# Main.net
KiCad netlist of a schematic drawn in Altium Designer
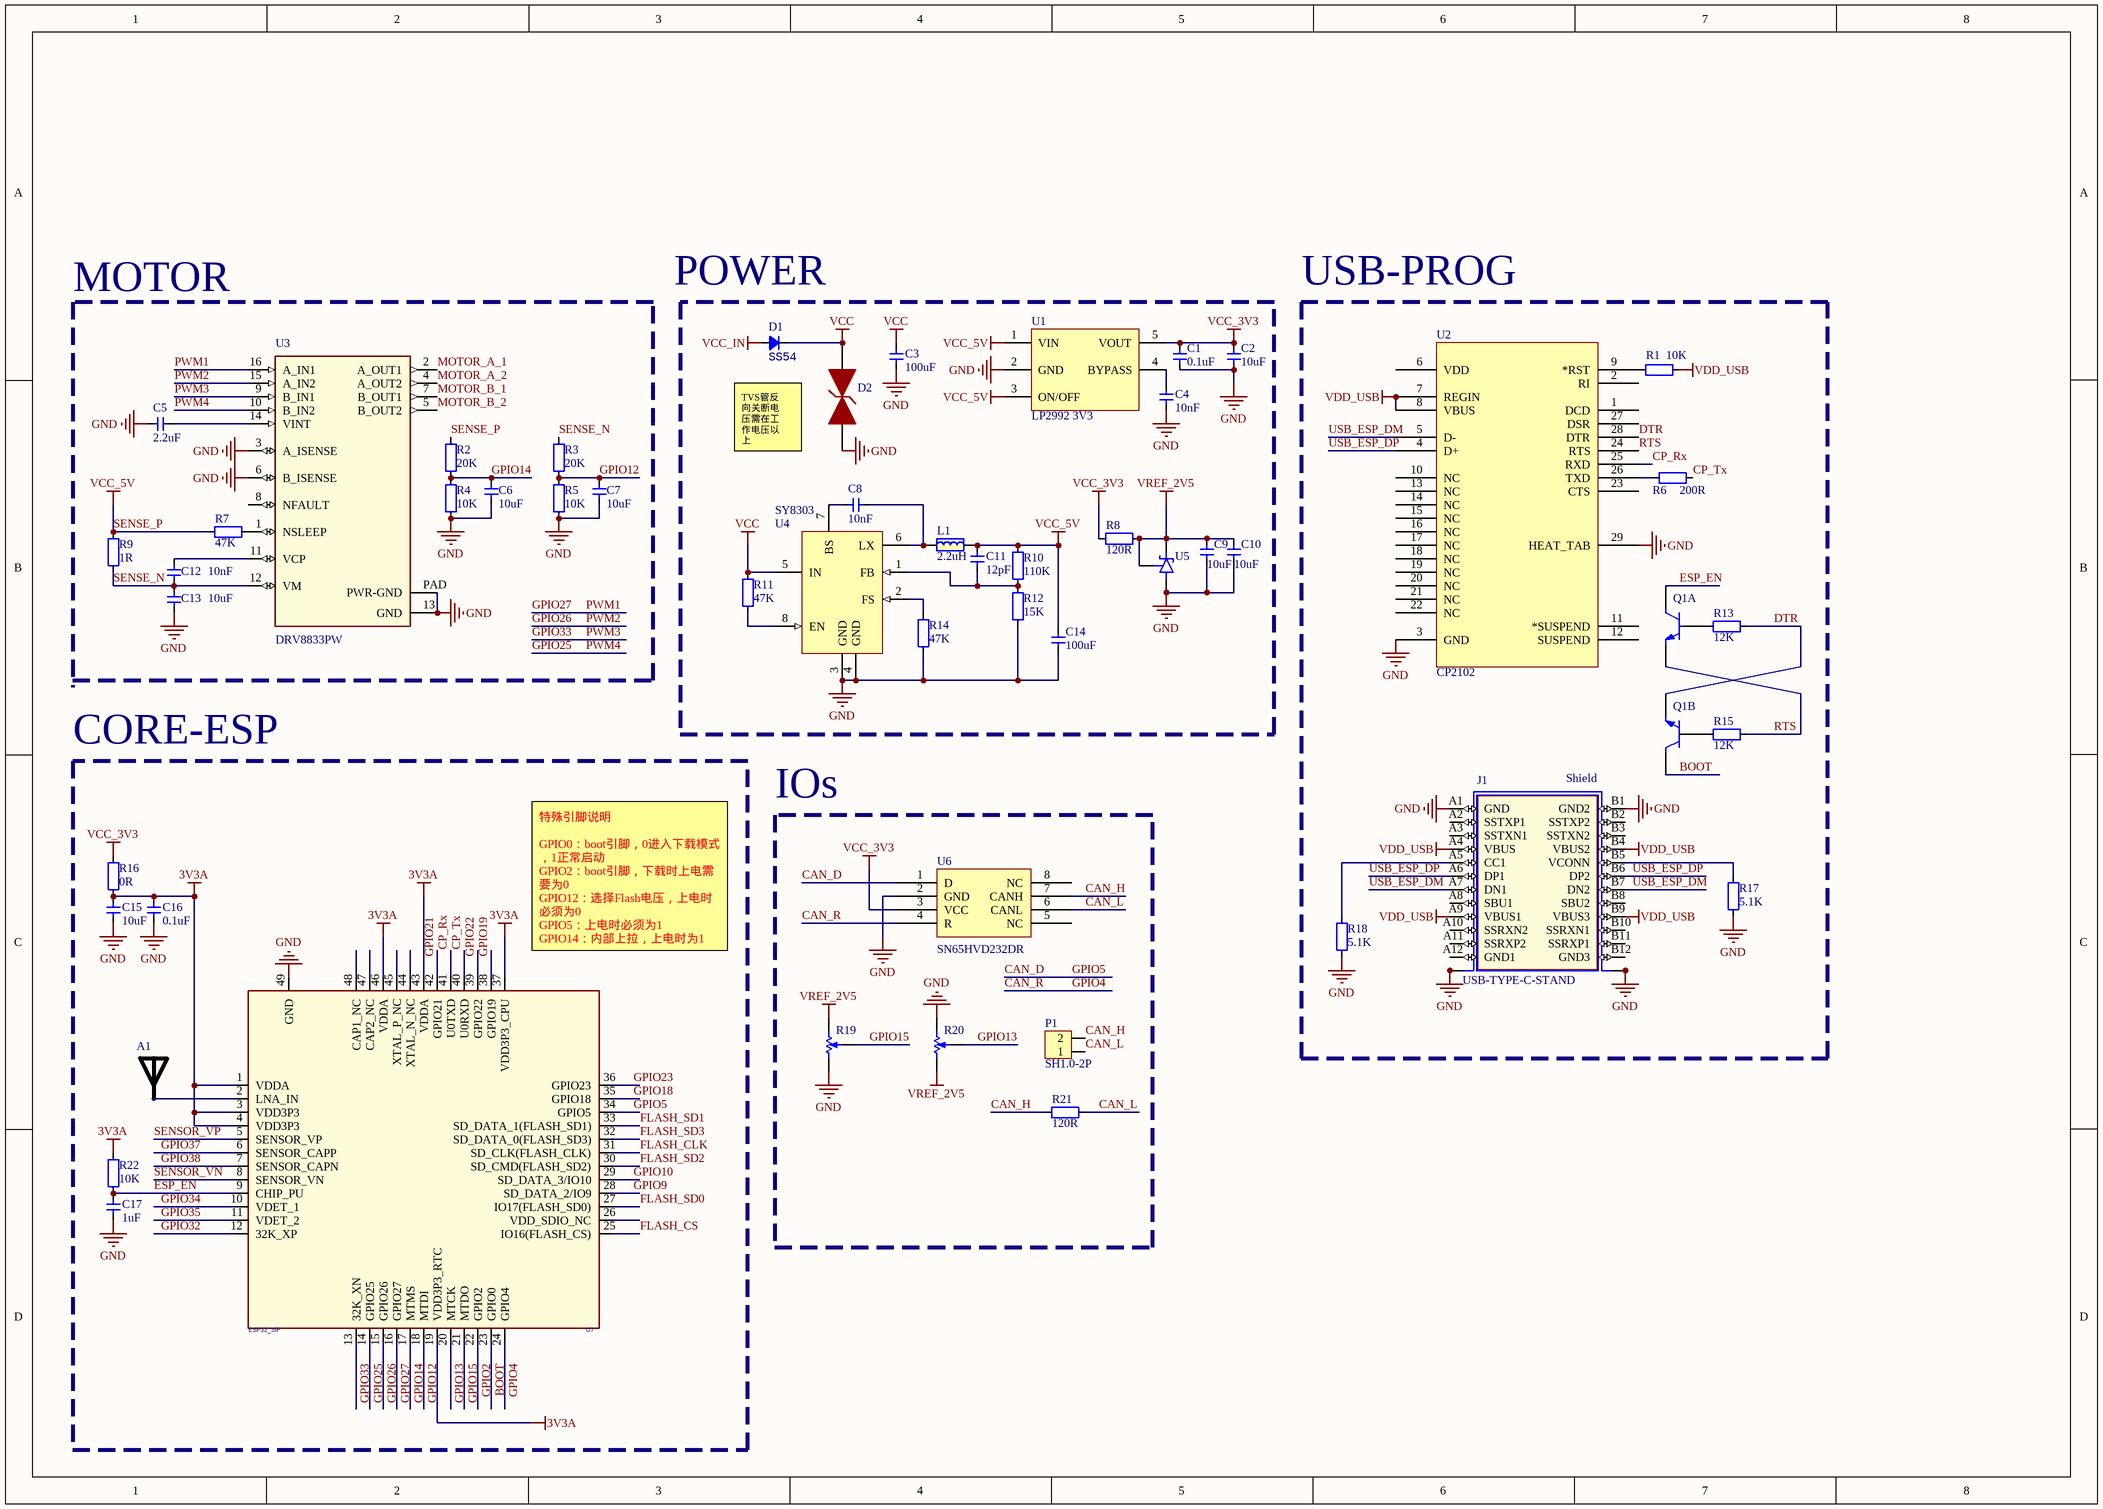
[diagram p0: Main.SchDoc]

(export (version "E")
  (design (tool "Eeschema 10.0.6"))
  (components
    (comp (ref "A1")
      (value "RAINSUN")
      (footprint "ANT-Rainsun-AN5120")
      (libsource (lib "MyPcbLib") (part "ANT-Rainsun-AP5120"))
    )
    (comp (ref "C1")
      (value "0.1uF")
      (footprint "CAP_0402")
      (description "Capacitor")
      (libsource (lib "MyPcbLib") (part "电容-0402"))
    )
    (comp (ref "C2")
      (value "10uF")
      (footprint "CAP_0402")
      (description "Capacitor")
      (libsource (lib "MyPcbLib") (part "电容-0402"))
    )
    (comp (ref "C3")
      (value "100uF")
      (footprint "1206-CAP")
      (description "Capacitor")
      (libsource (lib "MyPcbLib") (part "电容-1206"))
    )
    (comp (ref "C4")
      (value "10nF")
      (footprint "CAP_0402")
      (description "Capacitor")
      (libsource (lib "MyPcbLib") (part "电容-0402"))
    )
    (comp (ref "C5")
      (value "2.2uF")
      (footprint "CAP_0402")
      (description "Capacitor")
      (libsource (lib "MyPcbLib") (part "电容-0402"))
    )
    (comp (ref "C6")
      (value "10uF")
      (footprint "CAP_0402")
      (description "Capacitor")
      (libsource (lib "MyPcbLib") (part "电容-0402"))
    )
    (comp (ref "C7")
      (value "10uF")
      (footprint "CAP_0402")
      (description "Capacitor")
      (libsource (lib "MyPcbLib") (part "电容-0402"))
    )
    (comp (ref "C8")
      (value "10nF")
      (footprint "CAP_0402")
      (description "Capacitor")
      (libsource (lib "MyPcbLib") (part "电容-0402"))
    )
    (comp (ref "C9")
      (value "10uF")
      (footprint "CAP_0402")
      (description "Capacitor")
      (libsource (lib "MyPcbLib") (part "电容-0402"))
    )
    (comp (ref "C10")
      (value "10uF")
      (footprint "CAP_0402")
      (description "Capacitor")
      (libsource (lib "MyPcbLib") (part "电容-0402"))
    )
    (comp (ref "C11")
      (value "12pF")
      (footprint "CAP_0402")
      (description "Capacitor")
      (libsource (lib "MyPcbLib") (part "电容-0402"))
    )
    (comp (ref "C12")
      (value "10nF")
      (footprint "CAP_0402")
      (description "Capacitor")
      (libsource (lib "MyPcbLib") (part "电容-0402"))
    )
    (comp (ref "C13")
      (value "10uF")
      (footprint "CAP_0402")
      (description "Capacitor")
      (libsource (lib "MyPcbLib") (part "电容-0402"))
    )
    (comp (ref "C14")
      (value "100uF")
      (footprint "CAP_0402")
      (description "Capacitor")
      (libsource (lib "MyPcbLib") (part "电容-0402"))
    )
    (comp (ref "C15")
      (value "10uF")
      (footprint "CAP_0402")
      (description "Capacitor")
      (libsource (lib "MyPcbLib") (part "电容-0402"))
    )
    (comp (ref "C16")
      (value "0.1uF")
      (footprint "CAP_0402")
      (description "Capacitor")
      (libsource (lib "MyPcbLib") (part "电容-0402"))
    )
    (comp (ref "C17")
      (value "1uF")
      (footprint "CAP_0402")
      (description "Capacitor")
      (libsource (lib "MyPcbLib") (part "电容-0402"))
    )
    (comp (ref "D1")
      (value "SS54")
      (footprint "DO-214AC")
      (description "Diode")
      (libsource (lib "KitSprout") (part "Diode_SMA"))
    )
    (comp (ref "D2")
      (value "SMBJ28CA")
      (footprint "SMBJ-CA_MFG")
      (libsource (lib "MyPcbLib") (part "SMBJ28CA"))
    )
    (comp (ref "J1")
      (value "USB-TYPE-C-STAND")
      (footprint "USB-TYPE-C-STAND")
      (fields (field (name "MP") "632722110112") (field (name "MF") "Wurth Electronics"))
      (libsource (lib "MyPcbLib") (part "USB-TYPE-C-STAND"))
    )
    (comp (ref "L1") (value "2.2uH") (footprint "IND_CD74") (libsource (lib "MyPcbLib") (part "电感")))
    (comp (ref "P1") (value "SH1.0-2P") (footprint "SH1.0-2P") (libsource (lib "MyPcbLib") (part "SH1.0-2P")))
    (comp (ref "Q1")
      (value "BC847BVC-7")
      (footprint "SOT563-6")
      (libsource (lib "MyPcbLib") (part "BC847BVC-7"))
    )
    (comp (ref "R1")
      (value "10K")
      (footprint "RES_0402")
      (description "Resistor")
      (libsource (lib "") (part "电阻-0402_2"))
    )
    (comp (ref "R2")
      (value "20K")
      (footprint "RES_0402")
      (description "Resistor")
      (libsource (lib "") (part "电阻-0402_1"))
    )
    (comp (ref "R3")
      (value "20K")
      (footprint "RES_0402")
      (description "Resistor")
      (libsource (lib "") (part "电阻-0402_1"))
    )
    (comp (ref "R4")
      (value "10K")
      (footprint "RES_0402")
      (description "Resistor")
      (libsource (lib "") (part "电阻-0402_1"))
    )
    (comp (ref "R5")
      (value "10K")
      (footprint "RES_0402")
      (description "Resistor")
      (libsource (lib "") (part "电阻-0402_1"))
    )
    (comp (ref "R6")
      (value "200R")
      (footprint "RES_0402")
      (description "Resistor")
      (libsource (lib "") (part "电阻-0402_2"))
    )
    (comp (ref "R7")
      (value "47K")
      (footprint "RES_0402")
      (description "Resistor")
      (libsource (lib "") (part "电阻-0402_2"))
    )
    (comp (ref "R8")
      (value "120R")
      (footprint "RES_0402")
      (description "Resistor")
      (libsource (lib "") (part "电阻-0402_3"))
    )
    (comp (ref "R9")
      (value "1R")
      (footprint "1206-RES")
      (description "Resistor")
      (libsource (lib "MyPcbLib") (part "电阻-1206"))
    )
    (comp (ref "R10")
      (value "110K")
      (footprint "RES_0402")
      (description "Resistor")
      (libsource (lib "MyPcbLib") (part "电阻-0402"))
    )
    (comp (ref "R11")
      (value "47K")
      (footprint "RES_0402")
      (description "Resistor")
      (libsource (lib "MyPcbLib") (part "电阻-0402"))
    )
    (comp (ref "R12")
      (value "15K")
      (footprint "RES_0402")
      (description "Resistor")
      (libsource (lib "MyPcbLib") (part "电阻-0402"))
    )
    (comp (ref "R13")
      (value "12K")
      (footprint "RES_0402")
      (description "Resistor")
      (libsource (lib "") (part "电阻-0402_2"))
    )
    (comp (ref "R14")
      (value "47K")
      (footprint "RES_0402")
      (description "Resistor")
      (libsource (lib "MyPcbLib") (part "电阻-0402"))
    )
    (comp (ref "R15")
      (value "12K")
      (footprint "RES_0402")
      (description "Resistor")
      (libsource (lib "") (part "电阻-0402_2"))
    )
    (comp (ref "R16")
      (value "0R")
      (footprint "RES_0402")
      (description "Resistor")
      (libsource (lib "MyPcbLib") (part "电阻-0402"))
    )
    (comp (ref "R17")
      (value "5.1K")
      (footprint "RES_0402")
      (description "Resistor")
      (libsource (lib "MyPcbLib") (part "电阻-0402"))
    )
    (comp (ref "R18")
      (value "5.1K")
      (footprint "RES_0402")
      (description "Resistor")
      (libsource (lib "MyPcbLib") (part "电阻-0402"))
    )
    (comp (ref "R19")
      (value "ALPS-角度传感器")
      (footprint "ALPS-角度传感器")
      (fields (field (name "PUBLISHER") "Altium Limited"))
      (libsource (lib "MyPcbLib") (part "ALPS-角度传感器"))
    )
    (comp (ref "R20")
      (value "ALPS-角度传感器")
      (footprint "ALPS-角度传感器")
      (fields (field (name "PUBLISHER") "Altium Limited"))
      (libsource (lib "MyPcbLib") (part "ALPS-角度传感器"))
    )
    (comp (ref "R21")
      (value "120R")
      (footprint "RES_0402")
      (description "Resistor")
      (libsource (lib "") (part "电阻-0402_2"))
    )
    (comp (ref "R22")
      (value "10K")
      (footprint "RES_0402")
      (description "Resistor")
      (libsource (lib "MyPcbLib") (part "电阻-0402"))
    )
    (comp (ref "U1")
      (value "LP2992 3V3")
      (footprint "SOT23-5")
      (description "LDO")
      (libsource (lib "mLib") (part "LP2992"))
    )
    (comp (ref "U2")
      (value "CP2102")
      (footprint "QFN-28")
      (description "USB转TTL")
      (libsource (lib "mLib") (part "CP2102"))
    )
    (comp (ref "U3") (value "DRV8833PW") (footprint "TSSOP-16") (libsource (lib "mLib") (part "DRV8833PW")))
    (comp (ref "U4")
      (value "SY8303")
      (footprint "SOT23-8")
      (description "DC-DC")
      (fields
        (field (name "PARTNUMBER") "LT3469ETS8#TRMPBF")
        (field (name "MANUFACTURER") "Linear Technology")
      )
      (libsource (lib "MyPcbLib") (part "SY8303"))
    )
    (comp (ref "U5")
      (value "TL431IDBZT")
      (footprint "SOT23-3")
      (description "Adjustable precision shunt regulator 3-SOT-23 -40 to 85")
      (fields (field (name "MF") "Texas Instruments"))
      (libsource (lib "MyPcbLib") (part "TL431IDBZT"))
    )
    (comp (ref "U6")
      (value "SN65HVD232D")
      (footprint "SO-8")
      (fields
        (field (name "MANUFACTURER") "Texas Instruments")
        (field (name "MANUFACTURER PART NUMBER") "SN65HVD232DR")
      )
      (libsource (lib "MyPcbLib") (part "SN65HVD232D"))
    )
    (comp (ref "U7")
      (value "ESP32_SIP")
      (footprint "QFN-48_7X7")
      (libsource (lib "mLib") (part "ESP32-PICO"))
    )
  )
  (nets
    (net (code "1") (name "/BOOT") (class "Default")
      (node (ref "Q1") (pin "3") (pinfunction "C2_3") (pintype "passive"))
      (node (ref "U7") (pin "23") (pinfunction "GPIO0_23") (pintype "passive"))
    )
    (net (code "2") (name "/CAN_D") (class "Default")
      (node (ref "U6") (pin "1") (pinfunction "D_1") (pintype "passive"))
      (node (ref "U7") (pin "34") (pinfunction "GPIO5_34") (pintype "passive"))
    )
    (net (code "3") (name "/CAN_H") (class "Default")
      (node (ref "P1") (pin "2") (pinfunction "2_2") (pintype "passive"))
      (node (ref "R21") (pin "2") (pinfunction "2_2") (pintype "passive"))
      (node (ref "U6") (pin "7") (pinfunction "CANH_7") (pintype "passive"))
    )
    (net (code "4") (name "/CAN_L") (class "Default")
      (node (ref "P1") (pin "1") (pinfunction "1_1") (pintype "passive"))
      (node (ref "R21") (pin "1") (pinfunction "1_1") (pintype "passive"))
      (node (ref "U6") (pin "6") (pinfunction "CANL_6") (pintype "passive"))
    )
    (net (code "5") (name "/CAN_R") (class "Default")
      (node (ref "U6") (pin "4") (pinfunction "R_4") (pintype "passive"))
      (node (ref "U7") (pin "24") (pinfunction "GPIO4_24") (pintype "passive"))
    )
    (net (code "6") (name "/CP_Rx") (class "Default")
      (node (ref "U2") (pin "25") (pinfunction "RXD_25") (pintype "passive"))
      (node (ref "U7") (pin "41") (pinfunction "U0TXD_41") (pintype "power_in"))
    )
    (net (code "7") (name "/CP_Tx") (class "Default")
      (node (ref "R6") (pin "1") (pinfunction "1_1") (pintype "passive"))
      (node (ref "U7") (pin "40") (pinfunction "U0RXD_40") (pintype "power_in"))
    )
    (net (code "8") (name "/DTR") (class "Default")
      (node (ref "Q1") (pin "4") (pinfunction "E2_4") (pintype "passive"))
      (node (ref "R13") (pin "1") (pinfunction "1_1") (pintype "passive"))
      (node (ref "U2") (pin "28") (pinfunction "DTR_28") (pintype "passive"))
    )
    (net (code "9") (name "/ESP_EN") (class "Default")
      (node (ref "C17") (pin "1") (pinfunction "1_1") (pintype "passive"))
      (node (ref "Q1") (pin "6") (pinfunction "C1_6") (pintype "passive"))
      (node (ref "R22") (pin "2") (pinfunction "2_2") (pintype "passive"))
      (node (ref "U7") (pin "9") (pinfunction "CHIP_PU_9") (pintype "passive"))
    )
    (net (code "10") (name "/FLASH_CLK") (class "Default")
      (node (ref "U7") (pin "31") (pinfunction "SD_CLK(FLASH_CLK)_31") (pintype "passive"))
    )
    (net (code "11") (name "/FLASH_CS") (class "Default")
      (node (ref "U7") (pin "25") (pinfunction "IO16(FLASH_CS)_25") (pintype "passive"))
    )
    (net (code "12") (name "/FLASH_SD0") (class "Default")
      (node (ref "U7") (pin "27") (pinfunction "IO17(FLASH_SD0)_27") (pintype "passive"))
    )
    (net (code "13") (name "/FLASH_SD1") (class "Default")
      (node (ref "U7") (pin "33") (pinfunction "SD_DATA_1(FLASH_SD1)_33") (pintype "passive"))
    )
    (net (code "14") (name "/FLASH_SD2") (class "Default")
      (node (ref "U7") (pin "30") (pinfunction "SD_CMD(FLASH_SD2)_30") (pintype "passive"))
    )
    (net (code "15") (name "/FLASH_SD3") (class "Default")
      (node (ref "U7") (pin "32") (pinfunction "SD_DATA_0(FLASH_SD3)_32") (pintype "passive"))
    )
    (net (code "16") (name "/GPIO2") (class "Default")
      (node (ref "U7") (pin "22") (pinfunction "GPIO2_22") (pintype "passive"))
    )
    (net (code "17") (name "/GPIO9") (class "Default")
      (node (ref "U7") (pin "28") (pinfunction "SD_DATA_2/IO9_28") (pintype "passive"))
    )
    (net (code "18") (name "/GPIO10") (class "Default")
      (node (ref "U7") (pin "29") (pinfunction "SD_DATA_3/IO10_29") (pintype "passive"))
    )
    (net (code "19") (name "/GPIO12") (class "Default")
      (node (ref "C7") (pin "2") (pinfunction "2_2") (pintype "passive"))
      (node (ref "R3") (pin "1") (pinfunction "1_1") (pintype "passive"))
      (node (ref "R5") (pin "2") (pinfunction "2_2") (pintype "passive"))
      (node (ref "U7") (pin "18") (pinfunction "MTDI_18") (pintype "passive"))
    )
    (net (code "20") (name "/GPIO13") (class "Default")
      (node (ref "R20") (pin "2") (pinfunction "W_2") (pintype "passive"))
      (node (ref "U7") (pin "20") (pinfunction "MTCK_20") (pintype "passive"))
    )
    (net (code "21") (name "/GPIO14") (class "Default")
      (node (ref "C6") (pin "2") (pinfunction "2_2") (pintype "passive"))
      (node (ref "R2") (pin "1") (pinfunction "1_1") (pintype "passive"))
      (node (ref "R4") (pin "2") (pinfunction "2_2") (pintype "passive"))
      (node (ref "U7") (pin "17") (pinfunction "MTMS_17") (pintype "passive"))
    )
    (net (code "22") (name "/GPIO15") (class "Default")
      (node (ref "R19") (pin "2") (pinfunction "W_2") (pintype "passive"))
      (node (ref "U7") (pin "21") (pinfunction "MTDO_21") (pintype "passive"))
    )
    (net (code "23") (name "/GPIO18") (class "Default")
      (node (ref "U7") (pin "35") (pinfunction "GPIO18_35") (pintype "passive"))
    )
    (net (code "24") (name "/GPIO19") (class "Default")
      (node (ref "U7") (pin "38") (pinfunction "GPIO19_38") (pintype "passive"))
    )
    (net (code "25") (name "/GPIO21") (class "Default")
      (node (ref "U7") (pin "42") (pinfunction "GPIO21_42") (pintype "passive"))
    )
    (net (code "26") (name "/GPIO22") (class "Default")
      (node (ref "U7") (pin "39") (pinfunction "GPIO22_39") (pintype "passive"))
    )
    (net (code "27") (name "/GPIO23") (class "Default")
      (node (ref "U7") (pin "36") (pinfunction "GPIO23_36") (pintype "passive"))
    )
    (net (code "28") (name "/GPIO25") (class "Default")
      (node (ref "U3") (pin "10") (pinfunction "B_IN2_10") (pintype "input"))
      (node (ref "U7") (pin "14") (pinfunction "GPIO25_14") (pintype "passive"))
    )
    (net (code "29") (name "/GPIO26") (class "Default")
      (node (ref "U3") (pin "15") (pinfunction "A_IN2_15") (pintype "input"))
      (node (ref "U7") (pin "15") (pinfunction "GPIO26_15") (pintype "passive"))
    )
    (net (code "30") (name "/GPIO27") (class "Default")
      (node (ref "U3") (pin "16") (pinfunction "A_IN1_16") (pintype "input"))
      (node (ref "U7") (pin "16") (pinfunction "GPIO27_16") (pintype "passive"))
    )
    (net (code "31") (name "/GPIO32") (class "Default")
      (node (ref "U7") (pin "12") (pinfunction "32K_XP_12") (pintype "passive"))
    )
    (net (code "32") (name "/GPIO33") (class "Default")
      (node (ref "U3") (pin "9") (pinfunction "B_IN1_9") (pintype "input"))
      (node (ref "U7") (pin "13") (pinfunction "32K_XN_13") (pintype "passive"))
    )
    (net (code "33") (name "/GPIO34") (class "Default")
      (node (ref "U7") (pin "10") (pinfunction "VDET_1_10") (pintype "passive"))
    )
    (net (code "34") (name "/GPIO35") (class "Default")
      (node (ref "U7") (pin "11") (pinfunction "VDET_2_11") (pintype "passive"))
    )
    (net (code "35") (name "/GPIO37") (class "Default")
      (node (ref "U7") (pin "6") (pinfunction "SENSOR_CAPP_6") (pintype "passive"))
    )
    (net (code "36") (name "/GPIO38") (class "Default")
      (node (ref "U7") (pin "7") (pinfunction "SENSOR_CAPN_7") (pintype "passive"))
    )
    (net (code "37") (name "/MOTOR_A_1") (class "Default")
      (node (ref "U3") (pin "2") (pinfunction "A_OUT1_2") (pintype "output"))
    )
    (net (code "38") (name "/MOTOR_A_2") (class "Default")
      (node (ref "U3") (pin "4") (pinfunction "A_OUT2_4") (pintype "output"))
    )
    (net (code "39") (name "/MOTOR_B_1") (class "Default")
      (node (ref "U3") (pin "7") (pinfunction "B_OUT1_7") (pintype "output"))
    )
    (net (code "40") (name "/MOTOR_B_2") (class "Default")
      (node (ref "U3") (pin "5") (pinfunction "B_OUT2_5") (pintype "output"))
    )
    (net (code "41") (name "/RTS") (class "Default")
      (node (ref "Q1") (pin "1") (pinfunction "E1_1") (pintype "passive"))
      (node (ref "R15") (pin "1") (pinfunction "1_1") (pintype "passive"))
      (node (ref "U2") (pin "24") (pinfunction "RTS_24") (pintype "passive"))
    )
    (net (code "42") (name "/SENSE_N") (class "Default")
      (node (ref "C12") (pin "1") (pinfunction "1_1") (pintype "passive"))
      (node (ref "C13") (pin "2") (pinfunction "2_2") (pintype "passive"))
      (node (ref "R3") (pin "2") (pinfunction "2_2") (pintype "passive"))
      (node (ref "R9") (pin "1") (pinfunction "1_1") (pintype "passive"))
      (node (ref "U3") (pin "12") (pinfunction "VM_12") (pintype "bidirectional"))
    )
    (net (code "43") (name "/SENSOR_VN") (class "Default")
      (node (ref "U7") (pin "8") (pinfunction "SENSOR_VN_8") (pintype "passive"))
    )
    (net (code "44") (name "/SENSOR_VP") (class "Default")
      (node (ref "U7") (pin "5") (pinfunction "SENSOR_VP_5") (pintype "passive"))
    )
    (net (code "45") (name "/USB_ESP_DM") (class "Default")
      (node (ref "J1") (pin "A7") (pinfunction "DN1_A7") (pintype "bidirectional"))
      (node (ref "J1") (pin "B7") (pinfunction "DN2_B7") (pintype "bidirectional"))
      (node (ref "U2") (pin "5") (pinfunction "D-_5") (pintype "passive"))
    )
    (net (code "46") (name "/USB_ESP_DP") (class "Default")
      (node (ref "J1") (pin "A6") (pinfunction "DP1_A6") (pintype "bidirectional"))
      (node (ref "J1") (pin "B6") (pinfunction "DP2_B6") (pintype "bidirectional"))
      (node (ref "U2") (pin "4") (pinfunction "D+_4") (pintype "passive"))
    )
    (net (code "47") (name "3V3A") (class "Default")
      (node (ref "C15") (pin "2") (pinfunction "2_2") (pintype "passive"))
      (node (ref "C16") (pin "2") (pinfunction "2_2") (pintype "passive"))
      (node (ref "R16") (pin "2") (pinfunction "2_2") (pintype "passive"))
      (node (ref "R22") (pin "1") (pinfunction "1_1") (pintype "passive"))
      (node (ref "U7") (pin "1") (pinfunction "VDDA_1") (pintype "power_in"))
      (node (ref "U7") (pin "19") (pinfunction "VDD3P3_RTC_19") (pintype "power_in"))
      (node (ref "U7") (pin "3") (pinfunction "VDD3P3_3") (pintype "power_in"))
      (node (ref "U7") (pin "37") (pinfunction "VDD3P3_CPU_37") (pintype "power_in"))
      (node (ref "U7") (pin "4") (pinfunction "VDD3P3_4") (pintype "power_in"))
      (node (ref "U7") (pin "43") (pinfunction "VDDA_43") (pintype "power_in"))
      (node (ref "U7") (pin "46") (pinfunction "VDDA_46") (pintype "power_in"))
    )
    (net (code "48") (name "GND") (class "Default")
      (node (ref "C1") (pin "1") (pinfunction "1_1") (pintype "passive"))
      (node (ref "C10") (pin "1") (pinfunction "1_1") (pintype "passive"))
      (node (ref "C13") (pin "1") (pinfunction "1_1") (pintype "passive"))
      (node (ref "C14") (pin "1") (pinfunction "1_1") (pintype "passive"))
      (node (ref "C15") (pin "1") (pinfunction "1_1") (pintype "passive"))
      (node (ref "C16") (pin "1") (pinfunction "1_1") (pintype "passive"))
      (node (ref "C17") (pin "2") (pinfunction "2_2") (pintype "passive"))
      (node (ref "C2") (pin "1") (pinfunction "1_1") (pintype "passive"))
      (node (ref "C3") (pin "1") (pinfunction "1_1") (pintype "passive"))
      (node (ref "C4") (pin "1") (pinfunction "1_1") (pintype "passive"))
      (node (ref "C5") (pin "1") (pinfunction "1_1") (pintype "passive"))
      (node (ref "C6") (pin "1") (pinfunction "1_1") (pintype "passive"))
      (node (ref "C7") (pin "1") (pinfunction "1_1") (pintype "passive"))
      (node (ref "C9") (pin "1") (pinfunction "1_1") (pintype "passive"))
      (node (ref "D2") (pin "1") (pinfunction "1_1") (pintype "passive"))
      (node (ref "J1") (pin "A1") (pinfunction "GND_A1") (pintype "bidirectional"))
      (node (ref "J1") (pin "B1") (pinfunction "GND2_B1") (pintype "bidirectional"))
      (node (ref "J1") (pin "S1") (pinfunction "SHIELD_S1") (pintype "bidirectional"))
      (node (ref "J1") (pin "S2") (pinfunction "SHIELD_S2") (pintype "bidirectional"))
      (node (ref "J1") (pin "S3") (pinfunction "SHIELD1_S3") (pintype "bidirectional"))
      (node (ref "J1") (pin "S4") (pinfunction "SHIELD1_S4") (pintype "bidirectional"))
      (node (ref "R12") (pin "2") (pinfunction "2_2") (pintype "passive"))
      (node (ref "R14") (pin "2") (pinfunction "2_2") (pintype "passive"))
      (node (ref "R17") (pin "2") (pinfunction "2_2") (pintype "passive"))
      (node (ref "R18") (pin "2") (pinfunction "2_2") (pintype "passive"))
      (node (ref "R19") (pin "1") (pinfunction "-_1") (pintype "passive"))
      (node (ref "R20") (pin "3") (pinfunction "+_3") (pintype "passive"))
      (node (ref "R4") (pin "1") (pinfunction "1_1") (pintype "passive"))
      (node (ref "R5") (pin "1") (pinfunction "1_1") (pintype "passive"))
      (node (ref "U1") (pin "2") (pinfunction "GND_2") (pintype "passive"))
      (node (ref "U2") (pin "29") (pinfunction "HEAT_TAB_29") (pintype "passive"))
      (node (ref "U2") (pin "3") (pinfunction "GND_3") (pintype "passive"))
      (node (ref "U3") (pin "13") (pinfunction "GND_13") (pintype "power_in"))
      (node (ref "U3") (pin "3") (pinfunction "A_ISENSE_3") (pintype "bidirectional"))
      (node (ref "U3") (pin "6") (pinfunction "B_ISENSE_6") (pintype "bidirectional"))
      (node (ref "U3") (pin "PAD") (pinfunction "PWR-GND_PAD") (pintype "power_in"))
      (node (ref "U4") (pin "3") (pinfunction "GND_3") (pintype "power_in"))
      (node (ref "U4") (pin "4") (pinfunction "GND_4") (pintype "power_in"))
      (node (ref "U5") (pin "3") (pinfunction "ANODE_3") (pintype "passive"))
      (node (ref "U6") (pin "2") (pinfunction "GND_2") (pintype "passive"))
      (node (ref "U7") (pin "49") (pinfunction "GND_49") (pintype "power_in"))
    )
    (net (code "49") (name "Net-(J1-CC1)") (class "Default")
      (node (ref "J1") (pin "A5") (pinfunction "CC1_A5") (pintype "bidirectional"))
      (node (ref "R18") (pin "1") (pinfunction "1_1") (pintype "passive"))
    )
    (net (code "50") (name "Net-(J1-VCONN)") (class "Default")
      (node (ref "J1") (pin "B5") (pinfunction "VCONN_B5") (pintype "bidirectional"))
      (node (ref "R17") (pin "1") (pinfunction "1_1") (pintype "passive"))
    )
    (net (code "51") (name "Net-(Q1A-B1)") (class "Default")
      (node (ref "Q1") (pin "2") (pinfunction "B1_2") (pintype "passive"))
      (node (ref "R13") (pin "2") (pinfunction "2_2") (pintype "passive"))
    )
    (net (code "52") (name "Net-(Q1B-B2)") (class "Default")
      (node (ref "Q1") (pin "5") (pinfunction "B2_5") (pintype "passive"))
      (node (ref "R15") (pin "2") (pinfunction "2_2") (pintype "passive"))
    )
    (net (code "53") (name "Net-(U1-BYPASS)") (class "Default")
      (node (ref "C4") (pin "2") (pinfunction "2_2") (pintype "passive"))
      (node (ref "U1") (pin "4") (pinfunction "BYPASS_4") (pintype "passive"))
    )
    (net (code "54") (name "Net-(U2-*RST)") (class "Default")
      (node (ref "R1") (pin "2") (pinfunction "2_2") (pintype "passive"))
      (node (ref "U2") (pin "9") (pinfunction "*RST_9") (pintype "passive"))
    )
    (net (code "55") (name "Net-(U2-TXD)") (class "Default")
      (node (ref "R6") (pin "2") (pinfunction "2_2") (pintype "passive"))
      (node (ref "U2") (pin "26") (pinfunction "TXD_26") (pintype "passive"))
    )
    (net (code "56") (name "Net-(U3-NSLEEP)") (class "Default")
      (node (ref "R7") (pin "1") (pinfunction "1_1") (pintype "passive"))
      (node (ref "U3") (pin "1") (pinfunction "NSLEEP_1") (pintype "bidirectional"))
    )
    (net (code "57") (name "Net-(U3-VCP)") (class "Default")
      (node (ref "C12") (pin "2") (pinfunction "2_2") (pintype "passive"))
      (node (ref "U3") (pin "11") (pinfunction "VCP_11") (pintype "bidirectional"))
    )
    (net (code "58") (name "Net-(U3-VINT)") (class "Default")
      (node (ref "C5") (pin "2") (pinfunction "2_2") (pintype "passive"))
      (node (ref "U3") (pin "14") (pinfunction "VINT_14") (pintype "input"))
    )
    (net (code "59") (name "Net-(U4-BS)") (class "Default")
      (node (ref "C8") (pin "2") (pinfunction "2_2") (pintype "passive"))
      (node (ref "U4") (pin "7") (pinfunction "BS_7") (pintype "power_in"))
    )
    (net (code "60") (name "Net-(U4-EN)") (class "Default")
      (node (ref "R11") (pin "2") (pinfunction "2_2") (pintype "passive"))
      (node (ref "U4") (pin "8") (pinfunction "EN_8") (pintype "input"))
    )
    (net (code "61") (name "Net-(U4-FB)") (class "Default")
      (node (ref "C11") (pin "2") (pinfunction "2_2") (pintype "passive"))
      (node (ref "R10") (pin "2") (pinfunction "2_2") (pintype "passive"))
      (node (ref "R12") (pin "1") (pinfunction "1_1") (pintype "passive"))
      (node (ref "U4") (pin "1") (pinfunction "FB_1") (pintype "input"))
    )
    (net (code "62") (name "Net-(U4-FS)") (class "Default")
      (node (ref "R14") (pin "1") (pinfunction "1_1") (pintype "passive"))
      (node (ref "U4") (pin "2") (pinfunction "FS_2") (pintype "input"))
    )
    (net (code "63") (name "Net-(U4-LX)") (class "Default")
      (node (ref "C8") (pin "1") (pinfunction "1_1") (pintype "passive"))
      (node (ref "L1") (pin "1") (pinfunction "1_1") (pintype "passive"))
      (node (ref "U4") (pin "6") (pinfunction "LX_6") (pintype "power_in"))
    )
    (net (code "64") (name "Net-(U7-LNA_IN)") (class "Default")
      (node (ref "A1") (pin "1") (pinfunction "1_1") (pintype "passive"))
      (node (ref "U7") (pin "2") (pinfunction "LNA_IN_2") (pintype "passive"))
    )
    (net (code "65") (name "VCC") (class "Default")
      (node (ref "C3") (pin "2") (pinfunction "2_2") (pintype "passive"))
      (node (ref "D1") (pin "2") (pinfunction "K_2") (pintype "passive"))
      (node (ref "D2") (pin "2") (pinfunction "2_2") (pintype "passive"))
      (node (ref "R11") (pin "1") (pinfunction "1_1") (pintype "passive"))
      (node (ref "U4") (pin "5") (pinfunction "IN_5") (pintype "power_in"))
    )
    (net (code "66") (name "VCC_3V3") (class "Default")
      (node (ref "C1") (pin "2") (pinfunction "2_2") (pintype "passive"))
      (node (ref "C2") (pin "2") (pinfunction "2_2") (pintype "passive"))
      (node (ref "R16") (pin "1") (pinfunction "1_1") (pintype "passive"))
      (node (ref "R8") (pin "1") (pinfunction "1_1") (pintype "passive"))
      (node (ref "U1") (pin "5") (pinfunction "VOUT_5") (pintype "passive"))
      (node (ref "U6") (pin "3") (pinfunction "VCC_3") (pintype "passive"))
    )
    (net (code "67") (name "VCC_5V") (class "Default")
      (node (ref "C11") (pin "1") (pinfunction "1_1") (pintype "passive"))
      (node (ref "C14") (pin "2") (pinfunction "2_2") (pintype "passive"))
      (node (ref "L1") (pin "2") (pinfunction "2_2") (pintype "passive"))
      (node (ref "R10") (pin "1") (pinfunction "1_1") (pintype "passive"))
      (node (ref "R2") (pin "2") (pinfunction "2_2") (pintype "passive"))
      (node (ref "R7") (pin "2") (pinfunction "2_2") (pintype "passive"))
      (node (ref "R9") (pin "2") (pinfunction "2_2") (pintype "passive"))
      (node (ref "U1") (pin "1") (pinfunction "VIN_1") (pintype "passive"))
      (node (ref "U1") (pin "3") (pinfunction "ON/OFF_3") (pintype "passive"))
    )
    (net (code "68") (name "VCC_IN") (class "Default")
      (node (ref "D1") (pin "1") (pinfunction "A_1") (pintype "passive"))
    )
    (net (code "69") (name "VDD_USB") (class "Default")
      (node (ref "J1") (pin "A4") (pinfunction "VBUS_A4") (pintype "bidirectional"))
      (node (ref "J1") (pin "A9") (pinfunction "VBUS1_A9") (pintype "bidirectional"))
      (node (ref "J1") (pin "B4") (pinfunction "VBUS2_B4") (pintype "bidirectional"))
      (node (ref "J1") (pin "B9") (pinfunction "VBUS3_B9") (pintype "bidirectional"))
      (node (ref "R1") (pin "1") (pinfunction "1_1") (pintype "passive"))
      (node (ref "U2") (pin "7") (pinfunction "REGIN_7") (pintype "passive"))
      (node (ref "U2") (pin "8") (pinfunction "VBUS_8") (pintype "passive"))
    )
    (net (code "70") (name "VREF_2V5") (class "Default")
      (node (ref "C10") (pin "2") (pinfunction "2_2") (pintype "passive"))
      (node (ref "C9") (pin "2") (pinfunction "2_2") (pintype "passive"))
      (node (ref "R19") (pin "3") (pinfunction "+_3") (pintype "passive"))
      (node (ref "R20") (pin "1") (pinfunction "-_1") (pintype "passive"))
      (node (ref "R8") (pin "2") (pinfunction "2_2") (pintype "passive"))
      (node (ref "U5") (pin "1") (pinfunction "CATHODE_1") (pintype "passive"))
      (node (ref "U5") (pin "2") (pinfunction "REF_2") (pintype "passive"))
    )
    (net (code "71") (name "unconnected-(J1-GND1-PadA12)") (class "Default")
      (node (ref "J1") (pin "A12") (pinfunction "GND1_A12") (pintype "bidirectional"))
    )
    (net (code "72") (name "unconnected-(J1-GND3-PadB12)") (class "Default")
      (node (ref "J1") (pin "B12") (pinfunction "GND3_B12") (pintype "bidirectional"))
    )
    (net (code "73") (name "unconnected-(J1-SBU1-PadA8)") (class "Default")
      (node (ref "J1") (pin "A8") (pinfunction "SBU1_A8") (pintype "bidirectional"))
    )
    (net (code "74") (name "unconnected-(J1-SBU2-PadB8)") (class "Default")
      (node (ref "J1") (pin "B8") (pinfunction "SBU2_B8") (pintype "bidirectional"))
    )
    (net (code "75") (name "unconnected-(J1-SSRXN1-PadB10)") (class "Default")
      (node (ref "J1") (pin "B10") (pinfunction "SSRXN1_B10") (pintype "bidirectional"))
    )
    (net (code "76") (name "unconnected-(J1-SSRXN2-PadA10)") (class "Default")
      (node (ref "J1") (pin "A10") (pinfunction "SSRXN2_A10") (pintype "bidirectional"))
    )
    (net (code "77") (name "unconnected-(J1-SSRXP1-PadB11)") (class "Default")
      (node (ref "J1") (pin "B11") (pinfunction "SSRXP1_B11") (pintype "bidirectional"))
    )
    (net (code "78") (name "unconnected-(J1-SSRXP2-PadA11)") (class "Default")
      (node (ref "J1") (pin "A11") (pinfunction "SSRXP2_A11") (pintype "bidirectional"))
    )
    (net (code "79") (name "unconnected-(J1-SSTXN1-PadA3)") (class "Default")
      (node (ref "J1") (pin "A3") (pinfunction "SSTXN1_A3") (pintype "bidirectional"))
    )
    (net (code "80") (name "unconnected-(J1-SSTXN2-PadB3)") (class "Default")
      (node (ref "J1") (pin "B3") (pinfunction "SSTXN2_B3") (pintype "bidirectional"))
    )
    (net (code "81") (name "unconnected-(J1-SSTXP1-PadA2)") (class "Default")
      (node (ref "J1") (pin "A2") (pinfunction "SSTXP1_A2") (pintype "bidirectional"))
    )
    (net (code "82") (name "unconnected-(J1-SSTXP2-PadB2)") (class "Default")
      (node (ref "J1") (pin "B2") (pinfunction "SSTXP2_B2") (pintype "bidirectional"))
    )
    (net (code "83") (name "unconnected-(U2-*SUSPEND-Pad11)") (class "Default")
      (node (ref "U2") (pin "11") (pinfunction "*SUSPEND_11") (pintype "passive"))
    )
    (net (code "84") (name "unconnected-(U2-CTS-Pad23)") (class "Default")
      (node (ref "U2") (pin "23") (pinfunction "CTS_23") (pintype "passive"))
    )
    (net (code "85") (name "unconnected-(U2-DCD-Pad1)") (class "Default")
      (node (ref "U2") (pin "1") (pinfunction "DCD_1") (pintype "passive"))
    )
    (net (code "86") (name "unconnected-(U2-DSR-Pad27)") (class "Default")
      (node (ref "U2") (pin "27") (pinfunction "DSR_27") (pintype "passive"))
    )
    (net (code "87") (name "unconnected-(U2-NC-Pad10)") (class "Default")
      (node (ref "U2") (pin "10") (pinfunction "NC_10") (pintype "passive"))
    )
    (net (code "88") (name "unconnected-(U2-NC-Pad13)") (class "Default")
      (node (ref "U2") (pin "13") (pinfunction "NC_13") (pintype "passive"))
    )
    (net (code "89") (name "unconnected-(U2-NC-Pad14)") (class "Default")
      (node (ref "U2") (pin "14") (pinfunction "NC_14") (pintype "passive"))
    )
    (net (code "90") (name "unconnected-(U2-NC-Pad15)") (class "Default")
      (node (ref "U2") (pin "15") (pinfunction "NC_15") (pintype "passive"))
    )
    (net (code "91") (name "unconnected-(U2-NC-Pad16)") (class "Default")
      (node (ref "U2") (pin "16") (pinfunction "NC_16") (pintype "passive"))
    )
    (net (code "92") (name "unconnected-(U2-NC-Pad17)") (class "Default")
      (node (ref "U2") (pin "17") (pinfunction "NC_17") (pintype "passive"))
    )
    (net (code "93") (name "unconnected-(U2-NC-Pad18)") (class "Default")
      (node (ref "U2") (pin "18") (pinfunction "NC_18") (pintype "passive"))
    )
    (net (code "94") (name "unconnected-(U2-NC-Pad19)") (class "Default")
      (node (ref "U2") (pin "19") (pinfunction "NC_19") (pintype "passive"))
    )
    (net (code "95") (name "unconnected-(U2-NC-Pad20)") (class "Default")
      (node (ref "U2") (pin "20") (pinfunction "NC_20") (pintype "passive"))
    )
    (net (code "96") (name "unconnected-(U2-NC-Pad21)") (class "Default")
      (node (ref "U2") (pin "21") (pinfunction "NC_21") (pintype "passive"))
    )
    (net (code "97") (name "unconnected-(U2-NC-Pad22)") (class "Default")
      (node (ref "U2") (pin "22") (pinfunction "NC_22") (pintype "passive"))
    )
    (net (code "98") (name "unconnected-(U2-RI-Pad2)") (class "Default")
      (node (ref "U2") (pin "2") (pinfunction "RI_2") (pintype "passive"))
    )
    (net (code "99") (name "unconnected-(U2-SUSPEND-Pad12)") (class "Default")
      (node (ref "U2") (pin "12") (pinfunction "SUSPEND_12") (pintype "passive"))
    )
    (net (code "100") (name "unconnected-(U2-VDD-Pad6)") (class "Default")
      (node (ref "U2") (pin "6") (pinfunction "VDD_6") (pintype "passive"))
    )
    (net (code "101") (name "unconnected-(U3-NFAULT-Pad8)") (class "Default")
      (node (ref "U3") (pin "8") (pinfunction "NFAULT_8") (pintype "bidirectional"))
    )
    (net (code "102") (name "unconnected-(U6-NC-Pad5)") (class "Default")
      (node (ref "U6") (pin "5") (pinfunction "NC_5") (pintype "passive"))
    )
    (net (code "103") (name "unconnected-(U6-NC-Pad8)") (class "Default")
      (node (ref "U6") (pin "8") (pinfunction "NC_8") (pintype "passive"))
    )
    (net (code "104") (name "unconnected-(U7-CAP1_NC-Pad48)") (class "Default")
      (node (ref "U7") (pin "48") (pinfunction "CAP1_NC_48") (pintype "passive"))
    )
    (net (code "105") (name "unconnected-(U7-CAP2_NC-Pad47)") (class "Default")
      (node (ref "U7") (pin "47") (pinfunction "CAP2_NC_47") (pintype "passive"))
    )
    (net (code "106") (name "unconnected-(U7-VDD_SDIO_NC-Pad26)") (class "Default")
      (node (ref "U7") (pin "26") (pinfunction "VDD_SDIO_NC_26") (pintype "passive"))
    )
    (net (code "107") (name "unconnected-(U7-XTAL_N_NC-Pad44)") (class "Default")
      (node (ref "U7") (pin "44") (pinfunction "XTAL_N_NC_44") (pintype "passive"))
    )
    (net (code "108") (name "unconnected-(U7-XTAL_P_NC-Pad45)") (class "Default")
      (node (ref "U7") (pin "45") (pinfunction "XTAL_P_NC_45") (pintype "passive"))
    )
  )
)
